# KS0108_MCP23x17.net
KiCad netlist of a schematic drawn in EAGLE
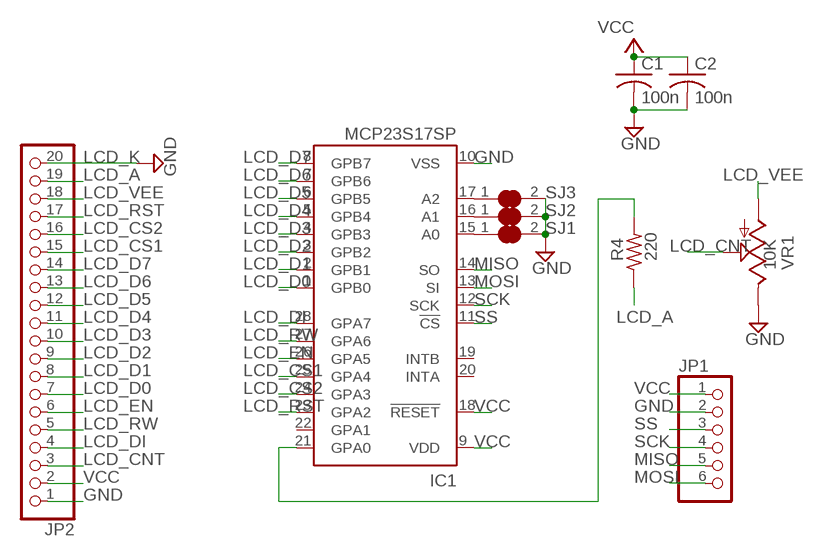
[diagram p0: schematic, sheet 1]

(export (version "E")
  (design (tool "Eeschema 10.0.6"))
  (components
    (comp (ref "C1")
      (value "100n")
      (footprint "eagle-import:C0805K")
      (libsource (lib "eagle-import") (part "C-USC0805K"))
    )
    (comp (ref "C2")
      (value "100n")
      (footprint "eagle-import:C0805K")
      (libsource (lib "eagle-import") (part "C-USC0805K"))
    )
    (comp (ref "IC1")
      (value "MCP23S17SP")
      (footprint "eagle-import:DIL28-3")
      (fields (field (name "MF") "MICROCHIP") (field (name "MPN") "MCP23S17-E/SP"))
      (libsource (lib "eagle-import") (part "MCP23S17SP"))
    )
    (comp (ref "JP1")
      (value "PINHD-1X6CB")
      (footprint "eagle-import:1X06-CLEANBIG")
      (libsource (lib "eagle-import") (part "PINHD-1X6CB"))
    )
    (comp (ref "JP2")
      (value "PINHD-1X20-BIG")
      (footprint "eagle-import:1X20-BIG")
      (libsource (lib "eagle-import") (part "PINHD-1X20-BIG"))
    )
    (comp (ref "R4")
      (value "220")
      (footprint "eagle-import:R0805")
      (libsource (lib "eagle-import") (part "R-US_R0805"))
    )
    (comp (ref "SJ1")
      (value "SOLDERJUMPER_CLOSED")
      (footprint "eagle-import:SOLDERJUMPER_CLOSEDWIRE")
      (libsource (lib "eagle-import") (part "SOLDERJUMPER_CLOSED"))
    )
    (comp (ref "SJ2")
      (value "SOLDERJUMPER_CLOSED")
      (footprint "eagle-import:SOLDERJUMPER_CLOSEDWIRE")
      (libsource (lib "eagle-import") (part "SOLDERJUMPER_CLOSED"))
    )
    (comp (ref "SJ3")
      (value "SOLDERJUMPER_CLOSED")
      (footprint "eagle-import:SOLDERJUMPER_CLOSEDWIRE")
      (libsource (lib "eagle-import") (part "SOLDERJUMPER_CLOSED"))
    )
    (comp (ref "VR1")
      (value "10K")
      (footprint "eagle-import:B25P")
      (libsource (lib "eagle-import") (part "TRIM_US-B25P"))
    )
  )
  (nets
    (net (code "1") (name "/LCD_A") (class "Default")
      (node (ref "JP2") (pin "19") (pinfunction "19_19") (pintype "passive"))
      (node (ref "R4") (pin "1") (pinfunction "1_1") (pintype "passive"))
    )
    (net (code "2") (name "/LCD_CNT") (class "Default")
      (node (ref "JP2") (pin "3") (pinfunction "3_3") (pintype "passive"))
      (node (ref "VR1") (pin "S") (pinfunction "S_S") (pintype "passive"))
    )
    (net (code "3") (name "/LCD_CS1") (class "Default")
      (node (ref "IC1") (pin "25") (pinfunction "GPA4_25") (pintype "bidirectional"))
      (node (ref "JP2") (pin "15") (pinfunction "15_15") (pintype "passive"))
    )
    (net (code "4") (name "/LCD_CS2") (class "Default")
      (node (ref "IC1") (pin "24") (pinfunction "GPA3_24") (pintype "bidirectional"))
      (node (ref "JP2") (pin "16") (pinfunction "16_16") (pintype "passive"))
    )
    (net (code "5") (name "/LCD_D0") (class "Default")
      (node (ref "IC1") (pin "1") (pinfunction "GPB0_1") (pintype "bidirectional"))
      (node (ref "JP2") (pin "7") (pinfunction "7_7") (pintype "passive"))
    )
    (net (code "6") (name "/LCD_D1") (class "Default")
      (node (ref "IC1") (pin "2") (pinfunction "GPB1_2") (pintype "bidirectional"))
      (node (ref "JP2") (pin "8") (pinfunction "8_8") (pintype "passive"))
    )
    (net (code "7") (name "/LCD_D2") (class "Default")
      (node (ref "IC1") (pin "3") (pinfunction "GPB2_3") (pintype "bidirectional"))
      (node (ref "JP2") (pin "9") (pinfunction "9_9") (pintype "passive"))
    )
    (net (code "8") (name "/LCD_D3") (class "Default")
      (node (ref "IC1") (pin "4") (pinfunction "GPB3_4") (pintype "bidirectional"))
      (node (ref "JP2") (pin "10") (pinfunction "10_10") (pintype "passive"))
    )
    (net (code "9") (name "/LCD_D4") (class "Default")
      (node (ref "IC1") (pin "5") (pinfunction "GPB4_5") (pintype "bidirectional"))
      (node (ref "JP2") (pin "11") (pinfunction "11_11") (pintype "passive"))
    )
    (net (code "10") (name "/LCD_D5") (class "Default")
      (node (ref "IC1") (pin "6") (pinfunction "GPB5_6") (pintype "bidirectional"))
      (node (ref "JP2") (pin "12") (pinfunction "12_12") (pintype "passive"))
    )
    (net (code "11") (name "/LCD_D6") (class "Default")
      (node (ref "IC1") (pin "7") (pinfunction "GPB6_7") (pintype "bidirectional"))
      (node (ref "JP2") (pin "13") (pinfunction "13_13") (pintype "passive"))
    )
    (net (code "12") (name "/LCD_D7") (class "Default")
      (node (ref "IC1") (pin "8") (pinfunction "GPB7_8") (pintype "bidirectional"))
      (node (ref "JP2") (pin "14") (pinfunction "14_14") (pintype "passive"))
    )
    (net (code "13") (name "/LCD_DI") (class "Default")
      (node (ref "IC1") (pin "28") (pinfunction "GPA7_28") (pintype "bidirectional"))
      (node (ref "JP2") (pin "4") (pinfunction "4_4") (pintype "passive"))
    )
    (net (code "14") (name "/LCD_EN") (class "Default")
      (node (ref "IC1") (pin "26") (pinfunction "GPA5_26") (pintype "bidirectional"))
      (node (ref "JP2") (pin "6") (pinfunction "6_6") (pintype "passive"))
    )
    (net (code "15") (name "/LCD_RST") (class "Default")
      (node (ref "IC1") (pin "23") (pinfunction "GPA2_23") (pintype "bidirectional"))
      (node (ref "JP2") (pin "17") (pinfunction "17_17") (pintype "passive"))
    )
    (net (code "16") (name "/LCD_RW") (class "Default")
      (node (ref "IC1") (pin "27") (pinfunction "GPA6_27") (pintype "bidirectional"))
      (node (ref "JP2") (pin "5") (pinfunction "5_5") (pintype "passive"))
    )
    (net (code "17") (name "/LCD_VEE") (class "Default")
      (node (ref "JP2") (pin "18") (pinfunction "18_18") (pintype "passive"))
      (node (ref "VR1") (pin "A") (pinfunction "A_A") (pintype "passive"))
    )
    (net (code "18") (name "/MISO") (class "Default")
      (node (ref "IC1") (pin "14") (pinfunction "SO_14") (pintype "output"))
      (node (ref "JP1") (pin "5") (pinfunction "5_5") (pintype "passive"))
    )
    (net (code "19") (name "/MOSI") (class "Default")
      (node (ref "IC1") (pin "13") (pinfunction "SI_13") (pintype "input"))
      (node (ref "JP1") (pin "6") (pinfunction "6_6") (pintype "passive"))
    )
    (net (code "20") (name "/SCK") (class "Default")
      (node (ref "IC1") (pin "12") (pinfunction "SCK_12") (pintype "input"))
      (node (ref "JP1") (pin "4") (pinfunction "4_4") (pintype "passive"))
    )
    (net (code "21") (name "/SS") (class "Default")
      (node (ref "IC1") (pin "11") (pinfunction "~{CS}_11") (pintype "input"))
      (node (ref "JP1") (pin "3") (pinfunction "3_3") (pintype "passive"))
    )
    (net (code "22") (name "GND") (class "Default")
      (node (ref "C1") (pin "2") (pinfunction "2_2") (pintype "passive"))
      (node (ref "C2") (pin "2") (pinfunction "2_2") (pintype "passive"))
      (node (ref "IC1") (pin "10") (pinfunction "VSS_10") (pintype "power_in"))
      (node (ref "JP1") (pin "2") (pinfunction "2_2") (pintype "passive"))
      (node (ref "JP2") (pin "1") (pinfunction "1_1") (pintype "passive"))
      (node (ref "JP2") (pin "20") (pinfunction "20_20") (pintype "passive"))
      (node (ref "SJ1") (pin "2") (pinfunction "2_2") (pintype "passive"))
      (node (ref "SJ2") (pin "2") (pinfunction "2_2") (pintype "passive"))
      (node (ref "SJ3") (pin "2") (pinfunction "2_2") (pintype "passive"))
      (node (ref "VR1") (pin "E") (pinfunction "E_E") (pintype "passive"))
    )
    (net (code "23") (name "Net-(IC1-A0)") (class "Default")
      (node (ref "IC1") (pin "15") (pinfunction "A0_15") (pintype "input"))
      (node (ref "SJ1") (pin "1") (pinfunction "1_1") (pintype "passive"))
    )
    (net (code "24") (name "Net-(IC1-A1)") (class "Default")
      (node (ref "IC1") (pin "16") (pinfunction "A1_16") (pintype "input"))
      (node (ref "SJ2") (pin "1") (pinfunction "1_1") (pintype "passive"))
    )
    (net (code "25") (name "Net-(IC1-A2)") (class "Default")
      (node (ref "IC1") (pin "17") (pinfunction "A2_17") (pintype "input"))
      (node (ref "SJ3") (pin "1") (pinfunction "1_1") (pintype "passive"))
    )
    (net (code "26") (name "Net-(IC1-GPA0)") (class "Default")
      (node (ref "IC1") (pin "21") (pinfunction "GPA0_21") (pintype "bidirectional"))
      (node (ref "R4") (pin "2") (pinfunction "2_2") (pintype "passive"))
    )
    (net (code "27") (name "VCC") (class "Default")
      (node (ref "C1") (pin "1") (pinfunction "1_1") (pintype "passive"))
      (node (ref "C2") (pin "1") (pinfunction "1_1") (pintype "passive"))
      (node (ref "IC1") (pin "18") (pinfunction "~{RESET}_18") (pintype "input"))
      (node (ref "IC1") (pin "9") (pinfunction "VDD_9") (pintype "power_in"))
      (node (ref "JP1") (pin "1") (pinfunction "1_1") (pintype "passive"))
      (node (ref "JP2") (pin "2") (pinfunction "2_2") (pintype "passive"))
    )
    (net (code "28") (name "unconnected-(IC1-GPA1-Pad22)") (class "Default")
      (node (ref "IC1") (pin "22") (pinfunction "GPA1_22") (pintype "bidirectional"))
    )
    (net (code "29") (name "unconnected-(IC1-INTA-Pad20)") (class "Default")
      (node (ref "IC1") (pin "20") (pinfunction "INTA_20") (pintype "output"))
    )
    (net (code "30") (name "unconnected-(IC1-INTB-Pad19)") (class "Default")
      (node (ref "IC1") (pin "19") (pinfunction "INTB_19") (pintype "output"))
    )
  )
)
